# I_measurement_lut.net
KiCad netlist of a schematic drawn in Altium Designer
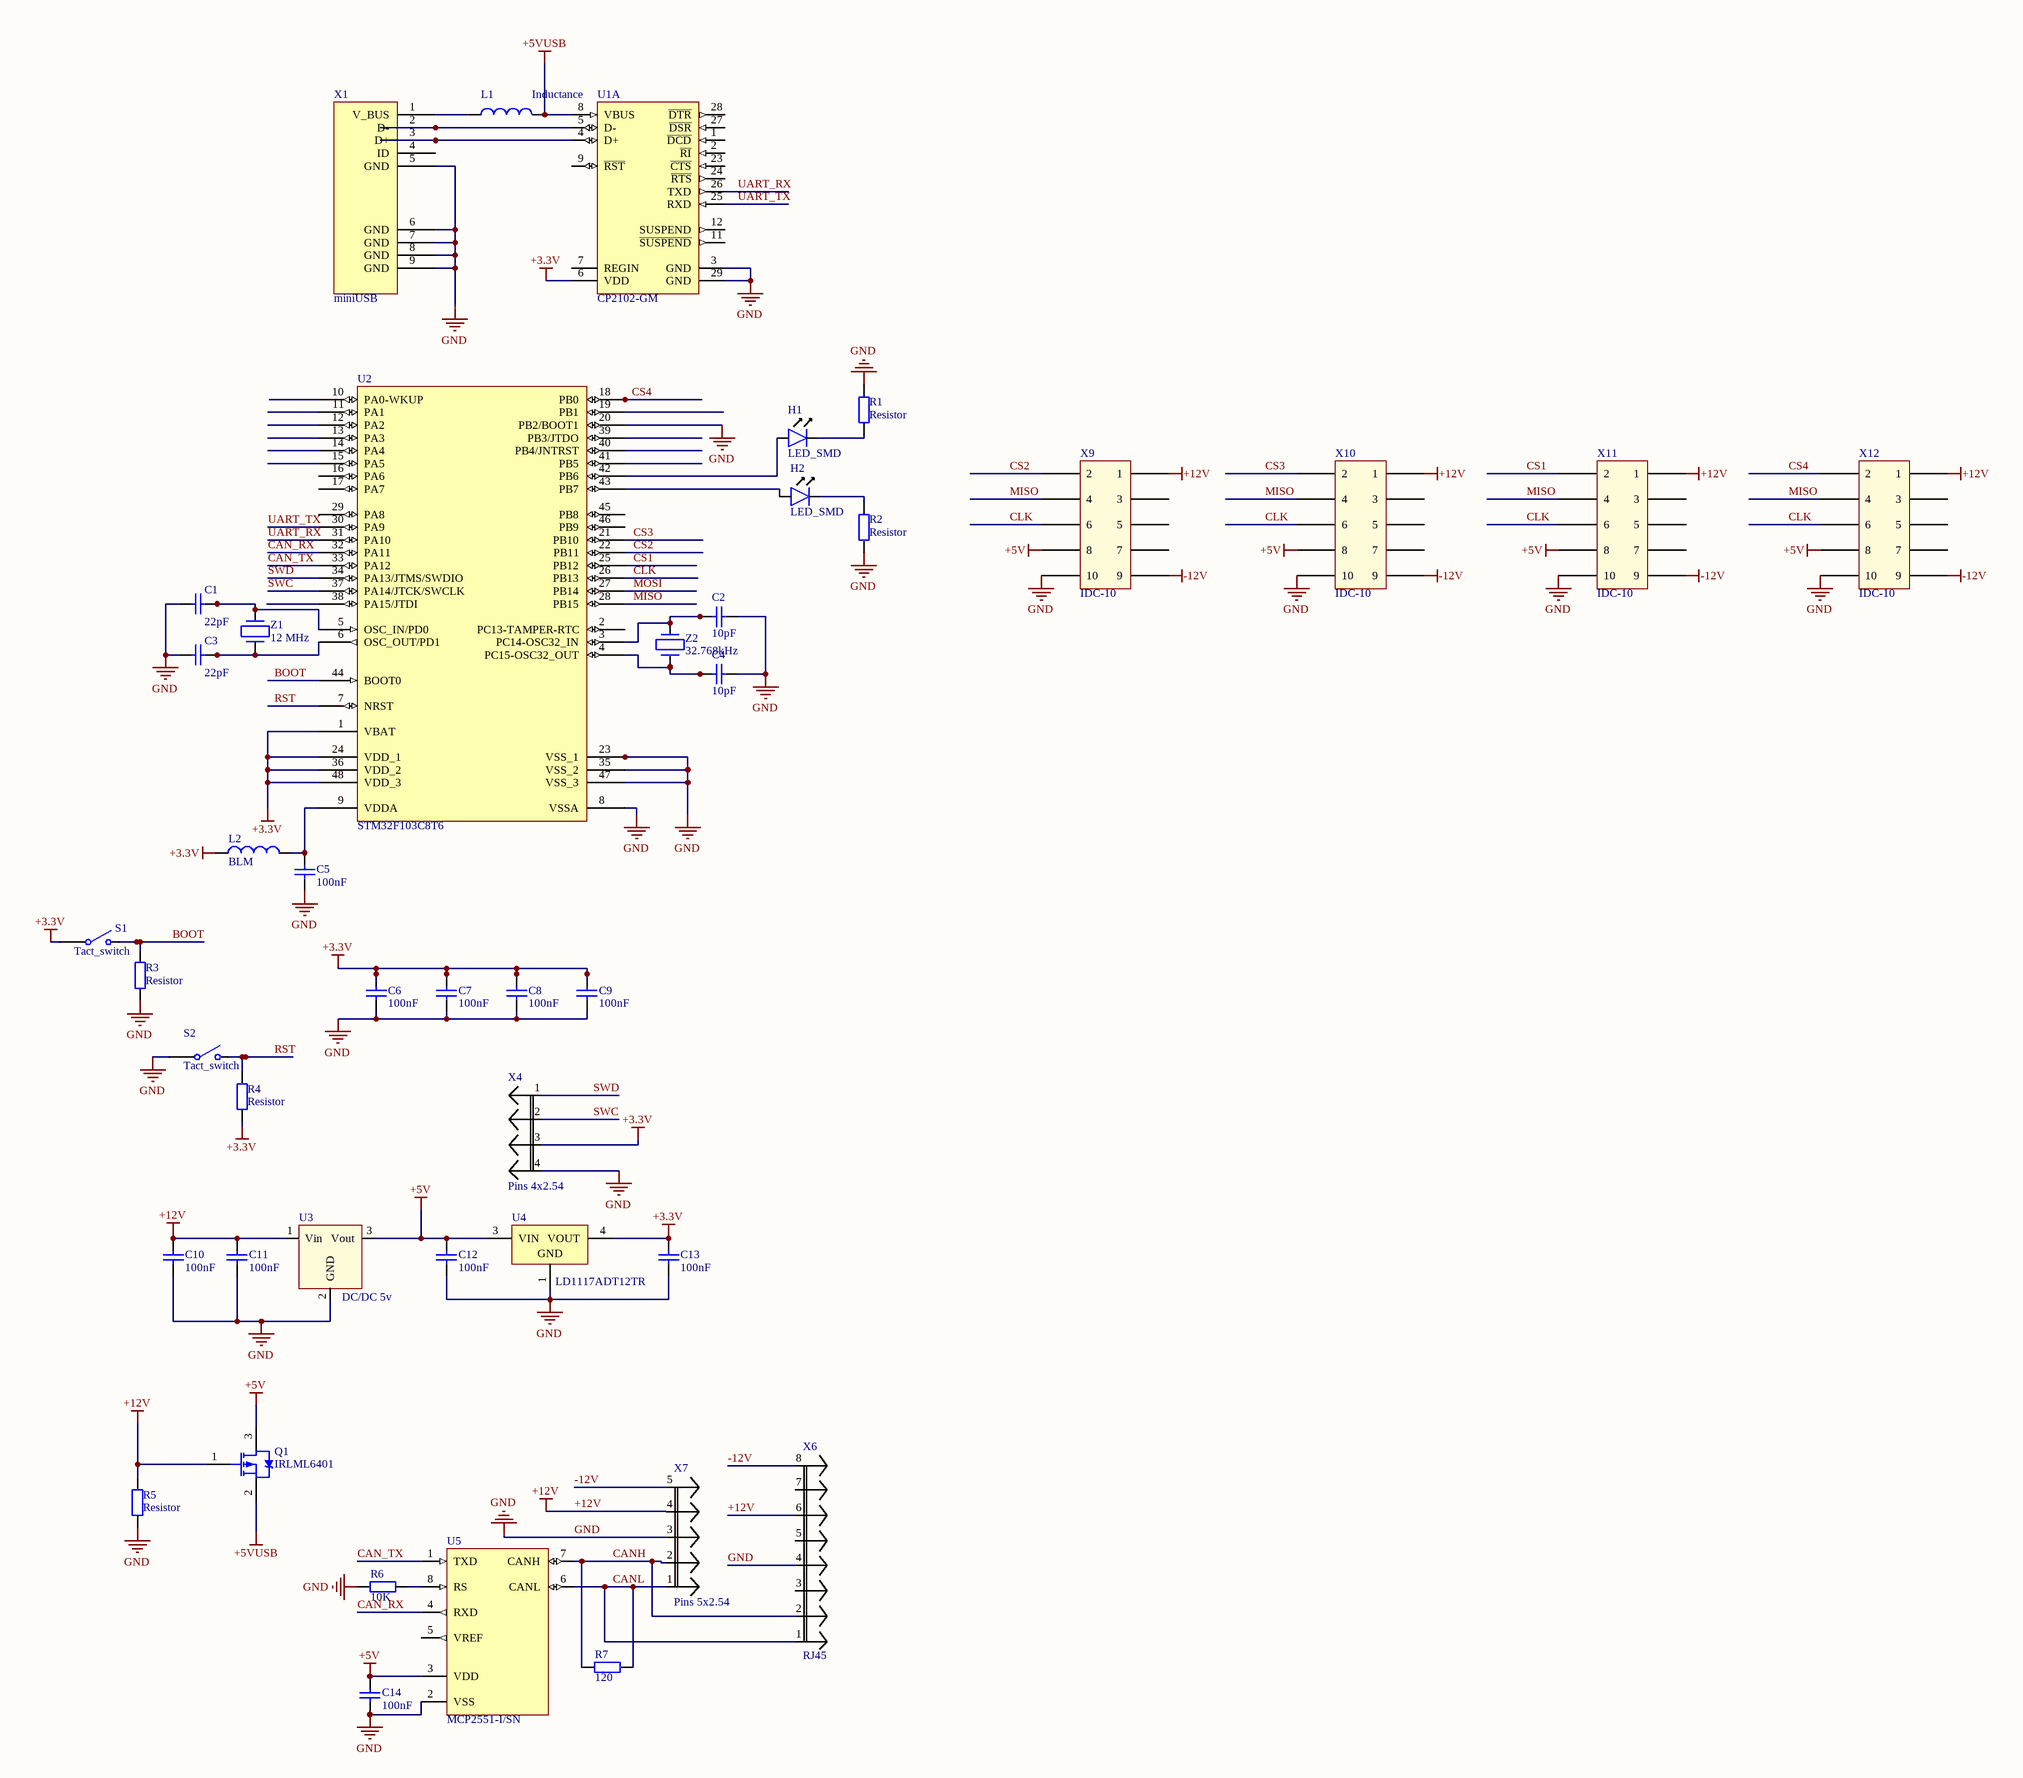
[diagram p0: I_measurement_lut.SchDoc]

(export (version "E")
  (design (tool "Eeschema 10.0.6"))
  (components
    (comp (ref "C1") (value "22pF") (footprint "C0805") (libsource (lib "A_H_sch_lib") (part "Condensator")))
    (comp (ref "C2") (value "10pF") (footprint "C0805") (libsource (lib "A_H_sch_lib") (part "Condensator")))
    (comp (ref "C3") (value "22pF") (footprint "C0805") (libsource (lib "A_H_sch_lib") (part "Condensator")))
    (comp (ref "C4") (value "10pF") (footprint "C0805") (libsource (lib "A_H_sch_lib") (part "Condensator")))
    (comp (ref "C5") (value "100nF") (footprint "C0805") (libsource (lib "A_H_sch_lib") (part "Condensator")))
    (comp (ref "C6") (value "100nF") (footprint "C0805") (libsource (lib "A_H_sch_lib") (part "Condensator")))
    (comp (ref "C7") (value "100nF") (footprint "C0805") (libsource (lib "A_H_sch_lib") (part "Condensator")))
    (comp (ref "C8") (value "100nF") (footprint "C0805") (libsource (lib "A_H_sch_lib") (part "Condensator")))
    (comp (ref "C9") (value "100nF") (footprint "C0805") (libsource (lib "A_H_sch_lib") (part "Condensator")))
    (comp (ref "C10")
      (value "100nF")
      (footprint "C0805")
      (libsource (lib "A_H_sch_lib") (part "Condensator"))
    )
    (comp (ref "C11")
      (value "100nF")
      (footprint "C0805")
      (libsource (lib "A_H_sch_lib") (part "Condensator"))
    )
    (comp (ref "C12")
      (value "100nF")
      (footprint "C0805")
      (libsource (lib "A_H_sch_lib") (part "Condensator"))
    )
    (comp (ref "C13")
      (value "100nF")
      (footprint "C0805")
      (libsource (lib "A_H_sch_lib") (part "Condensator"))
    )
    (comp (ref "C14")
      (value "100nF")
      (footprint "C0805")
      (libsource (lib "A_H_sch_lib") (part "Condensator"))
    )
    (comp (ref "H1") (value "LED_SMD") (footprint "C0805") (libsource (lib "A_H_sch_lib") (part "LED_SMD")))
    (comp (ref "H2") (value "LED_SMD") (footprint "C0805") (libsource (lib "A_H_sch_lib") (part "LED_SMD")))
    (comp (ref "L1")
      (value "Inductance")
      (footprint "L0805")
      (libsource (lib "A_H_sch_lib") (part "Inductance"))
    )
    (comp (ref "L2") (value "BLM") (footprint "L0805") (libsource (lib "A_H_sch_lib") (part "Inductance")))
    (comp (ref "Q1")
      (value "IRLML6401")
      (footprint "sot-23")
      (libsource (lib "A_H_sch_lib") (part "IRLML6401"))
    )
    (comp (ref "R1") (value "Resistor") (footprint "R0805") (libsource (lib "A_H_sch_lib") (part "Resistor")))
    (comp (ref "R2") (value "Resistor") (footprint "R0805") (libsource (lib "A_H_sch_lib") (part "Resistor")))
    (comp (ref "R3") (value "Resistor") (footprint "R0805") (libsource (lib "A_H_sch_lib") (part "Resistor")))
    (comp (ref "R4") (value "Resistor") (footprint "R0805") (libsource (lib "A_H_sch_lib") (part "Resistor")))
    (comp (ref "R5") (value "Resistor") (footprint "R0805") (libsource (lib "A_H_sch_lib") (part "Resistor")))
    (comp (ref "R6") (value "10K") (footprint "R0805") (libsource (lib "") (part "Resistor_1")))
    (comp (ref "R7") (value "120") (footprint "R0805") (libsource (lib "") (part "Resistor_2")))
    (comp (ref "S1")
      (value "Tact_switch")
      (footprint "Tact_switch_smd")
      (libsource (lib "A_H_sch_lib") (part "Tact_switch"))
    )
    (comp (ref "S2")
      (value "Tact_switch")
      (footprint "Tact_switch_smd")
      (libsource (lib "A_H_sch_lib") (part "Tact_switch"))
    )
    (comp (ref "U1")
      (value "CP2102-GM")
      (footprint "SLAB-QFN-28-3125x3125TP_N")
      (description "Single-Chip USB to UART Bridge, 1024 Bytes EEPROM, -40 to 85 degC, 28-pin QFN, Tube")
      (fields (field (name "MANUFACTURER") "Silicon Labs"))
      (libsource (lib "Silicon Labs Interface") (part "CP2102-GM"))
    )
    (comp (ref "U2")
      (value "STM32F103C8T6")
      (footprint "LQFP48_N")
      (description "STM32 ARM-based 32-bit MCU with 64 Kbytes Flash, 48-pin LQFP, Industrial Temperature")
      (fields (field (name "PUBLISHER") "Altium Limited"))
      (libsource (lib "ST Microcontroller 32-Bit STM32") (part "STM32F103C8T6"))
    )
    (comp (ref "U3")
      (value "DC/DC 5v")
      (footprint "A_H_pcb_lib:DC/DC R-78E")
      (libsource (lib "A_H_sch_lib") (part "DC/DC R-78E"))
    )
    (comp (ref "U4")
      (value "LD1117ADT12TR")
      (footprint "TO-252_N")
      (description "1A, Low Drop Positive Voltage Regulator, 1.2V, 3-Pin DPAK, Tape and Reel")
      (libsource (lib "STMicroelectronics Power Management Linear Regulator") (part "LD1117ADT12TR"))
    )
    (comp (ref "U5")
      (value "MCP2551-I/SN")
      (footprint "SOIC-SN8_N")
      (description "High-Speed CAN Transceiver, 8-Pin SOIC, Industrial Temperature")
      (fields (field (name "PUBLISHER") "Altium Limited"))
      (libsource (lib "Microchip Interface") (part "MCP2551-I/SN"))
    )
    (comp (ref "X1")
      (value "miniUSB")
      (footprint "A_H_pcb_lib:miniUSB")
      (libsource (lib "A_H_sch_lib") (part "miniUSB"))
    )
    (comp (ref "X4")
      (value "Pins 4x2.54")
      (footprint "Pins 4x2.54")
      (libsource (lib "A_H_sch_lib") (part "Pins 4x2.54"))
    )
    (comp (ref "X6")
      (value "RJ45")
      (footprint "A_H_pcb_lib:RJ45")
      (libsource (lib "A_H_sch_lib") (part "RJ45"))
    )
    (comp (ref "X7")
      (value "Pins 5x2.54")
      (footprint "Pins 5x2.54")
      (libsource (lib "A_H_sch_lib") (part "Pins 5x2.54"))
    )
    (comp (ref "X9")
      (value "IDC-10")
      (footprint "A_H_pcb_lib:IDC-10")
      (libsource (lib "A_H_sch_lib") (part "IDC-10"))
    )
    (comp (ref "X10")
      (value "IDC-10")
      (footprint "A_H_pcb_lib:IDC-10")
      (libsource (lib "A_H_sch_lib") (part "IDC-10"))
    )
    (comp (ref "X11")
      (value "IDC-10")
      (footprint "A_H_pcb_lib:IDC-10")
      (libsource (lib "A_H_sch_lib") (part "IDC-10"))
    )
    (comp (ref "X12")
      (value "IDC-10")
      (footprint "A_H_pcb_lib:IDC-10")
      (libsource (lib "A_H_sch_lib") (part "IDC-10"))
    )
    (comp (ref "Z1")
      (value "12 MHz")
      (footprint "kx 13 12MHz")
      (libsource (lib "A_H_sch_lib") (part "KX 13 Geyer"))
    )
    (comp (ref "Z2")
      (value "32.768kHz")
      (footprint "Geyer KX - 327S 32.768kHz")
      (libsource (lib "A_H_sch_lib") (part "Crystal Oscillator"))
    )
  )
  (nets
    (net (code "1") (name "+3.3V") (class "Default")
      (node (ref "C13") (pin "2") (pinfunction "2_2") (pintype "passive"))
      (node (ref "C6") (pin "2") (pinfunction "2_2") (pintype "passive"))
      (node (ref "C7") (pin "2") (pinfunction "2_2") (pintype "passive"))
      (node (ref "C8") (pin "2") (pinfunction "2_2") (pintype "passive"))
      (node (ref "C9") (pin "2") (pinfunction "2_2") (pintype "passive"))
      (node (ref "L2") (pin "1") (pinfunction "1_1") (pintype "passive"))
      (node (ref "R4") (pin "1") (pinfunction "1_1") (pintype "passive"))
      (node (ref "S1") (pin "1") (pinfunction "COMMON_1") (pintype "passive"))
      (node (ref "U1") (pin "6") (pinfunction "VDD_6") (pintype "power_in"))
      (node (ref "U2") (pin "1") (pinfunction "VBAT_1") (pintype "power_in"))
      (node (ref "U2") (pin "24") (pinfunction "VDD_1_24") (pintype "power_in"))
      (node (ref "U2") (pin "36") (pinfunction "VDD_2_36") (pintype "power_in"))
      (node (ref "U2") (pin "48") (pinfunction "VDD_3_48") (pintype "power_in"))
      (node (ref "U4") (pin "4") (pinfunction "VOUT_4") (pintype "power_in"))
      (node (ref "X4") (pin "3") (pinfunction "3_3") (pintype "passive"))
    )
    (net (code "2") (name "+5V") (class "Default")
      (node (ref "C12") (pin "2") (pinfunction "2_2") (pintype "passive"))
      (node (ref "C14") (pin "2") (pinfunction "2_2") (pintype "passive"))
      (node (ref "Q1") (pin "3") (pinfunction "D_3") (pintype "passive"))
      (node (ref "U3") (pin "3") (pinfunction "Vout_3") (pintype "passive"))
      (node (ref "U4") (pin "3") (pinfunction "VIN_3") (pintype "power_in"))
      (node (ref "U5") (pin "3") (pinfunction "VDD_3") (pintype "power_in"))
      (node (ref "X10") (pin "8") (pinfunction "8_8") (pintype "passive"))
      (node (ref "X11") (pin "8") (pinfunction "8_8") (pintype "passive"))
      (node (ref "X12") (pin "8") (pinfunction "8_8") (pintype "passive"))
      (node (ref "X9") (pin "8") (pinfunction "8_8") (pintype "passive"))
    )
    (net (code "3") (name "+5VUSB") (class "Default")
      (node (ref "L1") (pin "2") (pinfunction "2_2") (pintype "passive"))
      (node (ref "Q1") (pin "2") (pinfunction "S_2") (pintype "passive"))
      (node (ref "U1") (pin "8") (pinfunction "VBUS_8") (pintype "input"))
    )
    (net (code "4") (name "+12V") (class "Default")
      (node (ref "C10") (pin "2") (pinfunction "2_2") (pintype "passive"))
      (node (ref "C11") (pin "2") (pinfunction "2_2") (pintype "passive"))
      (node (ref "Q1") (pin "1") (pinfunction "G_1") (pintype "passive"))
      (node (ref "R5") (pin "2") (pinfunction "2_2") (pintype "passive"))
      (node (ref "U3") (pin "1") (pinfunction "Vin_1") (pintype "passive"))
      (node (ref "X10") (pin "1") (pinfunction "1_1") (pintype "passive"))
      (node (ref "X11") (pin "1") (pinfunction "1_1") (pintype "passive"))
      (node (ref "X12") (pin "1") (pinfunction "1_1") (pintype "passive"))
      (node (ref "X6") (pin "6") (pinfunction "6_6") (pintype "passive"))
      (node (ref "X7") (pin "4") (pinfunction "4_4") (pintype "passive"))
      (node (ref "X9") (pin "1") (pinfunction "1_1") (pintype "passive"))
    )
    (net (code "5") (name "-12V") (class "Default")
      (node (ref "X10") (pin "9") (pinfunction "9_9") (pintype "passive"))
      (node (ref "X11") (pin "9") (pinfunction "9_9") (pintype "passive"))
      (node (ref "X12") (pin "9") (pinfunction "9_9") (pintype "passive"))
      (node (ref "X6") (pin "8") (pinfunction "8_8") (pintype "passive"))
      (node (ref "X7") (pin "5") (pinfunction "5_5") (pintype "passive"))
      (node (ref "X9") (pin "9") (pinfunction "9_9") (pintype "passive"))
    )
    (net (code "6") (name "/BOOT") (class "Default")
      (node (ref "R3") (pin "2") (pinfunction "2_2") (pintype "passive"))
      (node (ref "S1") (pin "2") (pinfunction "NO_2") (pintype "passive"))
      (node (ref "U2") (pin "44") (pinfunction "BOOT0_44") (pintype "input"))
    )
    (net (code "7") (name "/CANH") (class "Default")
      (node (ref "R7") (pin "2") (pinfunction "2_2") (pintype "passive"))
      (node (ref "U5") (pin "7") (pinfunction "CANH_7") (pintype "bidirectional"))
      (node (ref "X6") (pin "2") (pinfunction "2_2") (pintype "passive"))
      (node (ref "X7") (pin "2") (pinfunction "2_2") (pintype "passive"))
    )
    (net (code "8") (name "/CANL") (class "Default")
      (node (ref "R7") (pin "1") (pinfunction "1_1") (pintype "passive"))
      (node (ref "U5") (pin "6") (pinfunction "CANL_6") (pintype "bidirectional"))
      (node (ref "X6") (pin "1") (pinfunction "1_1") (pintype "passive"))
      (node (ref "X7") (pin "1") (pinfunction "1_1") (pintype "passive"))
    )
    (net (code "9") (name "/CAN_RX") (class "Default")
      (node (ref "U2") (pin "32") (pinfunction "PA11_32") (pintype "bidirectional"))
      (node (ref "U5") (pin "4") (pinfunction "RXD_4") (pintype "output"))
    )
    (net (code "10") (name "/CAN_TX") (class "Default")
      (node (ref "U2") (pin "33") (pinfunction "PA12_33") (pintype "bidirectional"))
      (node (ref "U5") (pin "1") (pinfunction "TXD_1") (pintype "input"))
    )
    (net (code "11") (name "/CLK") (class "Default")
      (node (ref "U2") (pin "26") (pinfunction "PB13_26") (pintype "bidirectional"))
      (node (ref "X10") (pin "6") (pinfunction "6_6") (pintype "passive"))
      (node (ref "X11") (pin "6") (pinfunction "6_6") (pintype "passive"))
      (node (ref "X12") (pin "6") (pinfunction "6_6") (pintype "passive"))
      (node (ref "X9") (pin "6") (pinfunction "6_6") (pintype "passive"))
    )
    (net (code "12") (name "/CS1") (class "Default")
      (node (ref "U2") (pin "25") (pinfunction "PB12_25") (pintype "bidirectional"))
      (node (ref "X11") (pin "2") (pinfunction "2_2") (pintype "passive"))
    )
    (net (code "13") (name "/CS2") (class "Default")
      (node (ref "U2") (pin "22") (pinfunction "PB11_22") (pintype "bidirectional"))
      (node (ref "X9") (pin "2") (pinfunction "2_2") (pintype "passive"))
    )
    (net (code "14") (name "/CS3") (class "Default")
      (node (ref "U2") (pin "21") (pinfunction "PB10_21") (pintype "bidirectional"))
      (node (ref "X10") (pin "2") (pinfunction "2_2") (pintype "passive"))
    )
    (net (code "15") (name "/CS4") (class "Default")
      (node (ref "U2") (pin "18") (pinfunction "PB0_18") (pintype "bidirectional"))
      (node (ref "X12") (pin "2") (pinfunction "2_2") (pintype "passive"))
    )
    (net (code "16") (name "/MISO") (class "Default")
      (node (ref "U2") (pin "28") (pinfunction "PB15_28") (pintype "bidirectional"))
      (node (ref "X10") (pin "4") (pinfunction "4_4") (pintype "passive"))
      (node (ref "X11") (pin "4") (pinfunction "4_4") (pintype "passive"))
      (node (ref "X12") (pin "4") (pinfunction "4_4") (pintype "passive"))
      (node (ref "X9") (pin "4") (pinfunction "4_4") (pintype "passive"))
    )
    (net (code "17") (name "/MOSI") (class "Default")
      (node (ref "U2") (pin "27") (pinfunction "PB14_27") (pintype "bidirectional"))
    )
    (net (code "18") (name "/RST") (class "Default")
      (node (ref "R4") (pin "2") (pinfunction "2_2") (pintype "passive"))
      (node (ref "S2") (pin "2") (pinfunction "NO_2") (pintype "passive"))
      (node (ref "U2") (pin "7") (pinfunction "NRST_7") (pintype "bidirectional"))
    )
    (net (code "19") (name "/SWC") (class "Default")
      (node (ref "U2") (pin "37") (pinfunction "PA14/JTCK/SWCLK_37") (pintype "bidirectional"))
      (node (ref "X4") (pin "2") (pinfunction "2_2") (pintype "passive"))
    )
    (net (code "20") (name "/SWD") (class "Default")
      (node (ref "U2") (pin "34") (pinfunction "PA13/JTMS/SWDIO_34") (pintype "bidirectional"))
      (node (ref "X4") (pin "1") (pinfunction "1_1") (pintype "passive"))
    )
    (net (code "21") (name "/UART_RX") (class "Default")
      (node (ref "U1") (pin "26") (pinfunction "TXD_26") (pintype "output"))
      (node (ref "U2") (pin "31") (pinfunction "PA10_31") (pintype "bidirectional"))
    )
    (net (code "22") (name "/UART_TX") (class "Default")
      (node (ref "U1") (pin "25") (pinfunction "RXD_25") (pintype "input"))
      (node (ref "U2") (pin "30") (pinfunction "PA9_30") (pintype "bidirectional"))
    )
    (net (code "23") (name "GND") (class "Default")
      (node (ref "C1") (pin "1") (pinfunction "1_1") (pintype "passive"))
      (node (ref "C10") (pin "1") (pinfunction "1_1") (pintype "passive"))
      (node (ref "C11") (pin "1") (pinfunction "1_1") (pintype "passive"))
      (node (ref "C12") (pin "1") (pinfunction "1_1") (pintype "passive"))
      (node (ref "C13") (pin "1") (pinfunction "1_1") (pintype "passive"))
      (node (ref "C14") (pin "1") (pinfunction "1_1") (pintype "passive"))
      (node (ref "C2") (pin "1") (pinfunction "1_1") (pintype "passive"))
      (node (ref "C3") (pin "1") (pinfunction "1_1") (pintype "passive"))
      (node (ref "C4") (pin "1") (pinfunction "1_1") (pintype "passive"))
      (node (ref "C5") (pin "1") (pinfunction "1_1") (pintype "passive"))
      (node (ref "C6") (pin "1") (pinfunction "1_1") (pintype "passive"))
      (node (ref "C7") (pin "1") (pinfunction "1_1") (pintype "passive"))
      (node (ref "C8") (pin "1") (pinfunction "1_1") (pintype "passive"))
      (node (ref "C9") (pin "1") (pinfunction "1_1") (pintype "passive"))
      (node (ref "R1") (pin "2") (pinfunction "2_2") (pintype "passive"))
      (node (ref "R2") (pin "1") (pinfunction "1_1") (pintype "passive"))
      (node (ref "R3") (pin "1") (pinfunction "1_1") (pintype "passive"))
      (node (ref "R5") (pin "1") (pinfunction "1_1") (pintype "passive"))
      (node (ref "R6") (pin "1") (pinfunction "1_1") (pintype "passive"))
      (node (ref "S2") (pin "1") (pinfunction "COMMON_1") (pintype "passive"))
      (node (ref "U1") (pin "29") (pinfunction "GND_29") (pintype "power_in"))
      (node (ref "U1") (pin "3") (pinfunction "GND_3") (pintype "power_in"))
      (node (ref "U2") (pin "20") (pinfunction "PB2/BOOT1_20") (pintype "bidirectional"))
      (node (ref "U2") (pin "23") (pinfunction "VSS_1_23") (pintype "power_in"))
      (node (ref "U2") (pin "35") (pinfunction "VSS_2_35") (pintype "power_in"))
      (node (ref "U2") (pin "47") (pinfunction "VSS_3_47") (pintype "power_in"))
      (node (ref "U2") (pin "8") (pinfunction "VSSA_8") (pintype "power_in"))
      (node (ref "U3") (pin "2") (pinfunction "GND_2") (pintype "passive"))
      (node (ref "U4") (pin "1") (pinfunction "GND_1") (pintype "power_in"))
      (node (ref "U5") (pin "2") (pinfunction "VSS_2") (pintype "power_in"))
      (node (ref "X1") (pin "5") (pinfunction "GND_5") (pintype "passive"))
      (node (ref "X1") (pin "6") (pinfunction "GND_6") (pintype "passive"))
      (node (ref "X1") (pin "7") (pinfunction "GND_7") (pintype "passive"))
      (node (ref "X1") (pin "8") (pinfunction "GND_8") (pintype "passive"))
      (node (ref "X1") (pin "9") (pinfunction "GND_9") (pintype "passive"))
      (node (ref "X10") (pin "10") (pinfunction "10_10") (pintype "passive"))
      (node (ref "X11") (pin "10") (pinfunction "10_10") (pintype "passive"))
      (node (ref "X12") (pin "10") (pinfunction "10_10") (pintype "passive"))
      (node (ref "X4") (pin "4") (pinfunction "4_4") (pintype "passive"))
      (node (ref "X6") (pin "4") (pinfunction "4_4") (pintype "passive"))
      (node (ref "X7") (pin "3") (pinfunction "3_3") (pintype "passive"))
      (node (ref "X9") (pin "10") (pinfunction "10_10") (pintype "passive"))
    )
    (net (code "24") (name "Net-(H1-Pad2)") (class "Default")
      (node (ref "H1") (pin "2") (pinfunction "2_2") (pintype "passive"))
      (node (ref "R1") (pin "1") (pinfunction "1_1") (pintype "passive"))
    )
    (net (code "25") (name "Net-(H2-Pad2)") (class "Default")
      (node (ref "H2") (pin "2") (pinfunction "2_2") (pintype "passive"))
      (node (ref "R2") (pin "2") (pinfunction "2_2") (pintype "passive"))
    )
    (net (code "26") (name "Net-(U1A-D+)") (class "Default")
      (node (ref "U1") (pin "4") (pinfunction "D+_4") (pintype "bidirectional"))
      (node (ref "X1") (pin "3") (pinfunction "D+_3") (pintype "passive"))
    )
    (net (code "27") (name "Net-(U1A-D-)") (class "Default")
      (node (ref "U1") (pin "5") (pinfunction "D-_5") (pintype "bidirectional"))
      (node (ref "X1") (pin "2") (pinfunction "D-_2") (pintype "passive"))
    )
    (net (code "28") (name "Net-(U2-OSC_IN{slash}PD0)") (class "Default")
      (node (ref "C1") (pin "2") (pinfunction "2_2") (pintype "passive"))
      (node (ref "U2") (pin "5") (pinfunction "OSC_IN/PD0_5") (pintype "input"))
      (node (ref "Z1") (pin "1") (pinfunction "1_1") (pintype "passive"))
    )
    (net (code "29") (name "Net-(U2-OSC_OUT{slash}PD1)") (class "Default")
      (node (ref "C3") (pin "2") (pinfunction "2_2") (pintype "passive"))
      (node (ref "U2") (pin "6") (pinfunction "OSC_OUT/PD1_6") (pintype "output"))
      (node (ref "Z1") (pin "3") (pinfunction "3_3") (pintype "passive"))
    )
    (net (code "30") (name "Net-(U2-PB6)") (class "Default")
      (node (ref "H1") (pin "1") (pinfunction "1_1") (pintype "passive"))
      (node (ref "U2") (pin "42") (pinfunction "PB6_42") (pintype "bidirectional"))
    )
    (net (code "31") (name "Net-(U2-PB7)") (class "Default")
      (node (ref "H2") (pin "1") (pinfunction "1_1") (pintype "passive"))
      (node (ref "U2") (pin "43") (pinfunction "PB7_43") (pintype "bidirectional"))
    )
    (net (code "32") (name "Net-(U2-PC14-OSC32_IN)") (class "Default")
      (node (ref "C2") (pin "2") (pinfunction "2_2") (pintype "passive"))
      (node (ref "U2") (pin "3") (pinfunction "PC14-OSC32_IN_3") (pintype "bidirectional"))
      (node (ref "Z2") (pin "1") (pinfunction "1_1") (pintype "passive"))
    )
    (net (code "33") (name "Net-(U2-PC15-OSC32_OUT)") (class "Default")
      (node (ref "C4") (pin "2") (pinfunction "2_2") (pintype "passive"))
      (node (ref "U2") (pin "4") (pinfunction "PC15-OSC32_OUT_4") (pintype "bidirectional"))
      (node (ref "Z2") (pin "2") (pinfunction "2_2") (pintype "passive"))
    )
    (net (code "34") (name "Net-(U2-VDDA)") (class "Default")
      (node (ref "C5") (pin "2") (pinfunction "2_2") (pintype "passive"))
      (node (ref "L2") (pin "2") (pinfunction "2_2") (pintype "passive"))
      (node (ref "U2") (pin "9") (pinfunction "VDDA_9") (pintype "power_in"))
    )
    (net (code "35") (name "Net-(U5-RS)") (class "Default")
      (node (ref "R6") (pin "2") (pinfunction "2_2") (pintype "passive"))
      (node (ref "U5") (pin "8") (pinfunction "RS_8") (pintype "input"))
    )
    (net (code "36") (name "Net-(X1-V_BUS)") (class "Default")
      (node (ref "L1") (pin "1") (pinfunction "1_1") (pintype "passive"))
      (node (ref "X1") (pin "1") (pinfunction "V_BUS_1") (pintype "passive"))
    )
    (net (code "37") (name "unconnected-(U1A-REGIN-Pad7)") (class "Default")
      (node (ref "U1") (pin "7") (pinfunction "REGIN_7") (pintype "power_in"))
    )
    (net (code "38") (name "unconnected-(U1A-SUSPEND-Pad12)") (class "Default")
      (node (ref "U1") (pin "12") (pinfunction "SUSPEND_12") (pintype "output"))
    )
    (net (code "39") (name "unconnected-(U1A-~{CTS}-Pad23)") (class "Default")
      (node (ref "U1") (pin "23") (pinfunction "~{CTS}_23") (pintype "input"))
    )
    (net (code "40") (name "unconnected-(U1A-~{DCD}-Pad1)") (class "Default")
      (node (ref "U1") (pin "1") (pinfunction "~{DCD}_1") (pintype "input"))
    )
    (net (code "41") (name "unconnected-(U1A-~{DSR}-Pad27)") (class "Default")
      (node (ref "U1") (pin "27") (pinfunction "~{DSR}_27") (pintype "input"))
    )
    (net (code "42") (name "unconnected-(U1A-~{DTR}-Pad28)") (class "Default")
      (node (ref "U1") (pin "28") (pinfunction "~{DTR}_28") (pintype "output"))
    )
    (net (code "43") (name "unconnected-(U1A-~{RI}-Pad2)") (class "Default")
      (node (ref "U1") (pin "2") (pinfunction "~{RI}_2") (pintype "input"))
    )
    (net (code "44") (name "unconnected-(U1A-~{RST}-Pad9)") (class "Default")
      (node (ref "U1") (pin "9") (pinfunction "~{RST}_9") (pintype "bidirectional"))
    )
    (net (code "45") (name "unconnected-(U1A-~{RTS}-Pad24)") (class "Default")
      (node (ref "U1") (pin "24") (pinfunction "~{RTS}_24") (pintype "output"))
    )
    (net (code "46") (name "unconnected-(U1A-~{SUSPEND}-Pad11)") (class "Default")
      (node (ref "U1") (pin "11") (pinfunction "~{SUSPEND}_11") (pintype "output"))
    )
    (net (code "47") (name "unconnected-(U2-PA0-WKUP-Pad10)") (class "Default")
      (node (ref "U2") (pin "10") (pinfunction "PA0-WKUP_10") (pintype "bidirectional"))
    )
    (net (code "48") (name "unconnected-(U2-PA1-Pad11)") (class "Default")
      (node (ref "U2") (pin "11") (pinfunction "PA1_11") (pintype "bidirectional"))
    )
    (net (code "49") (name "unconnected-(U2-PA2-Pad12)") (class "Default")
      (node (ref "U2") (pin "12") (pinfunction "PA2_12") (pintype "bidirectional"))
    )
    (net (code "50") (name "unconnected-(U2-PA3-Pad13)") (class "Default")
      (node (ref "U2") (pin "13") (pinfunction "PA3_13") (pintype "bidirectional"))
    )
    (net (code "51") (name "unconnected-(U2-PA4-Pad14)") (class "Default")
      (node (ref "U2") (pin "14") (pinfunction "PA4_14") (pintype "bidirectional"))
    )
    (net (code "52") (name "unconnected-(U2-PA5-Pad15)") (class "Default")
      (node (ref "U2") (pin "15") (pinfunction "PA5_15") (pintype "bidirectional"))
    )
    (net (code "53") (name "unconnected-(U2-PA6-Pad16)") (class "Default")
      (node (ref "U2") (pin "16") (pinfunction "PA6_16") (pintype "bidirectional"))
    )
    (net (code "54") (name "unconnected-(U2-PA7-Pad17)") (class "Default")
      (node (ref "U2") (pin "17") (pinfunction "PA7_17") (pintype "bidirectional"))
    )
    (net (code "55") (name "unconnected-(U2-PA8-Pad29)") (class "Default")
      (node (ref "U2") (pin "29") (pinfunction "PA8_29") (pintype "bidirectional"))
    )
    (net (code "56") (name "unconnected-(U2-PA15{slash}JTDI-Pad38)") (class "Default")
      (node (ref "U2") (pin "38") (pinfunction "PA15/JTDI_38") (pintype "bidirectional"))
    )
    (net (code "57") (name "unconnected-(U2-PB1-Pad19)") (class "Default")
      (node (ref "U2") (pin "19") (pinfunction "PB1_19") (pintype "bidirectional"))
    )
    (net (code "58") (name "unconnected-(U2-PB3{slash}JTDO-Pad39)") (class "Default")
      (node (ref "U2") (pin "39") (pinfunction "PB3/JTDO_39") (pintype "bidirectional"))
    )
    (net (code "59") (name "unconnected-(U2-PB4{slash}JNTRST-Pad40)") (class "Default")
      (node (ref "U2") (pin "40") (pinfunction "PB4/JNTRST_40") (pintype "bidirectional"))
    )
    (net (code "60") (name "unconnected-(U2-PB5-Pad41)") (class "Default")
      (node (ref "U2") (pin "41") (pinfunction "PB5_41") (pintype "bidirectional"))
    )
    (net (code "61") (name "unconnected-(U2-PB8-Pad45)") (class "Default")
      (node (ref "U2") (pin "45") (pinfunction "PB8_45") (pintype "bidirectional"))
    )
    (net (code "62") (name "unconnected-(U2-PB9-Pad46)") (class "Default")
      (node (ref "U2") (pin "46") (pinfunction "PB9_46") (pintype "bidirectional"))
    )
    (net (code "63") (name "unconnected-(U2-PC13-TAMPER-RTC-Pad2)") (class "Default")
      (node (ref "U2") (pin "2") (pinfunction "PC13-TAMPER-RTC_2") (pintype "bidirectional"))
    )
    (net (code "64") (name "unconnected-(U5-VREF-Pad5)") (class "Default")
      (node (ref "U5") (pin "5") (pinfunction "VREF_5") (pintype "output"))
    )
    (net (code "65") (name "unconnected-(X1-ID-Pad4)") (class "Default")
      (node (ref "X1") (pin "4") (pinfunction "ID_4") (pintype "passive"))
    )
    (net (code "66") (name "unconnected-(X6-Pad3)") (class "Default")
      (node (ref "X6") (pin "3") (pinfunction "3_3") (pintype "passive"))
    )
    (net (code "67") (name "unconnected-(X6-Pad5)") (class "Default")
      (node (ref "X6") (pin "5") (pinfunction "5_5") (pintype "passive"))
    )
    (net (code "68") (name "unconnected-(X6-Pad7)") (class "Default")
      (node (ref "X6") (pin "7") (pinfunction "7_7") (pintype "passive"))
    )
    (net (code "69") (name "unconnected-(X9-Pad3)") (class "Default")
      (node (ref "X9") (pin "3") (pinfunction "3_3") (pintype "passive"))
    )
    (net (code "70") (name "unconnected-(X9-Pad5)") (class "Default")
      (node (ref "X9") (pin "5") (pinfunction "5_5") (pintype "passive"))
    )
    (net (code "71") (name "unconnected-(X9-Pad7)") (class "Default")
      (node (ref "X9") (pin "7") (pinfunction "7_7") (pintype "passive"))
    )
    (net (code "72") (name "unconnected-(X10-Pad3)") (class "Default")
      (node (ref "X10") (pin "3") (pinfunction "3_3") (pintype "passive"))
    )
    (net (code "73") (name "unconnected-(X10-Pad5)") (class "Default")
      (node (ref "X10") (pin "5") (pinfunction "5_5") (pintype "passive"))
    )
    (net (code "74") (name "unconnected-(X10-Pad7)") (class "Default")
      (node (ref "X10") (pin "7") (pinfunction "7_7") (pintype "passive"))
    )
    (net (code "75") (name "unconnected-(X11-Pad3)") (class "Default")
      (node (ref "X11") (pin "3") (pinfunction "3_3") (pintype "passive"))
    )
    (net (code "76") (name "unconnected-(X11-Pad5)") (class "Default")
      (node (ref "X11") (pin "5") (pinfunction "5_5") (pintype "passive"))
    )
    (net (code "77") (name "unconnected-(X11-Pad7)") (class "Default")
      (node (ref "X11") (pin "7") (pinfunction "7_7") (pintype "passive"))
    )
    (net (code "78") (name "unconnected-(X12-Pad3)") (class "Default")
      (node (ref "X12") (pin "3") (pinfunction "3_3") (pintype "passive"))
    )
    (net (code "79") (name "unconnected-(X12-Pad5)") (class "Default")
      (node (ref "X12") (pin "5") (pinfunction "5_5") (pintype "passive"))
    )
    (net (code "80") (name "unconnected-(X12-Pad7)") (class "Default")
      (node (ref "X12") (pin "7") (pinfunction "7_7") (pintype "passive"))
    )
  )
)
